# UNO-R3.net
KiCad netlist of a schematic drawn in Altium Designer
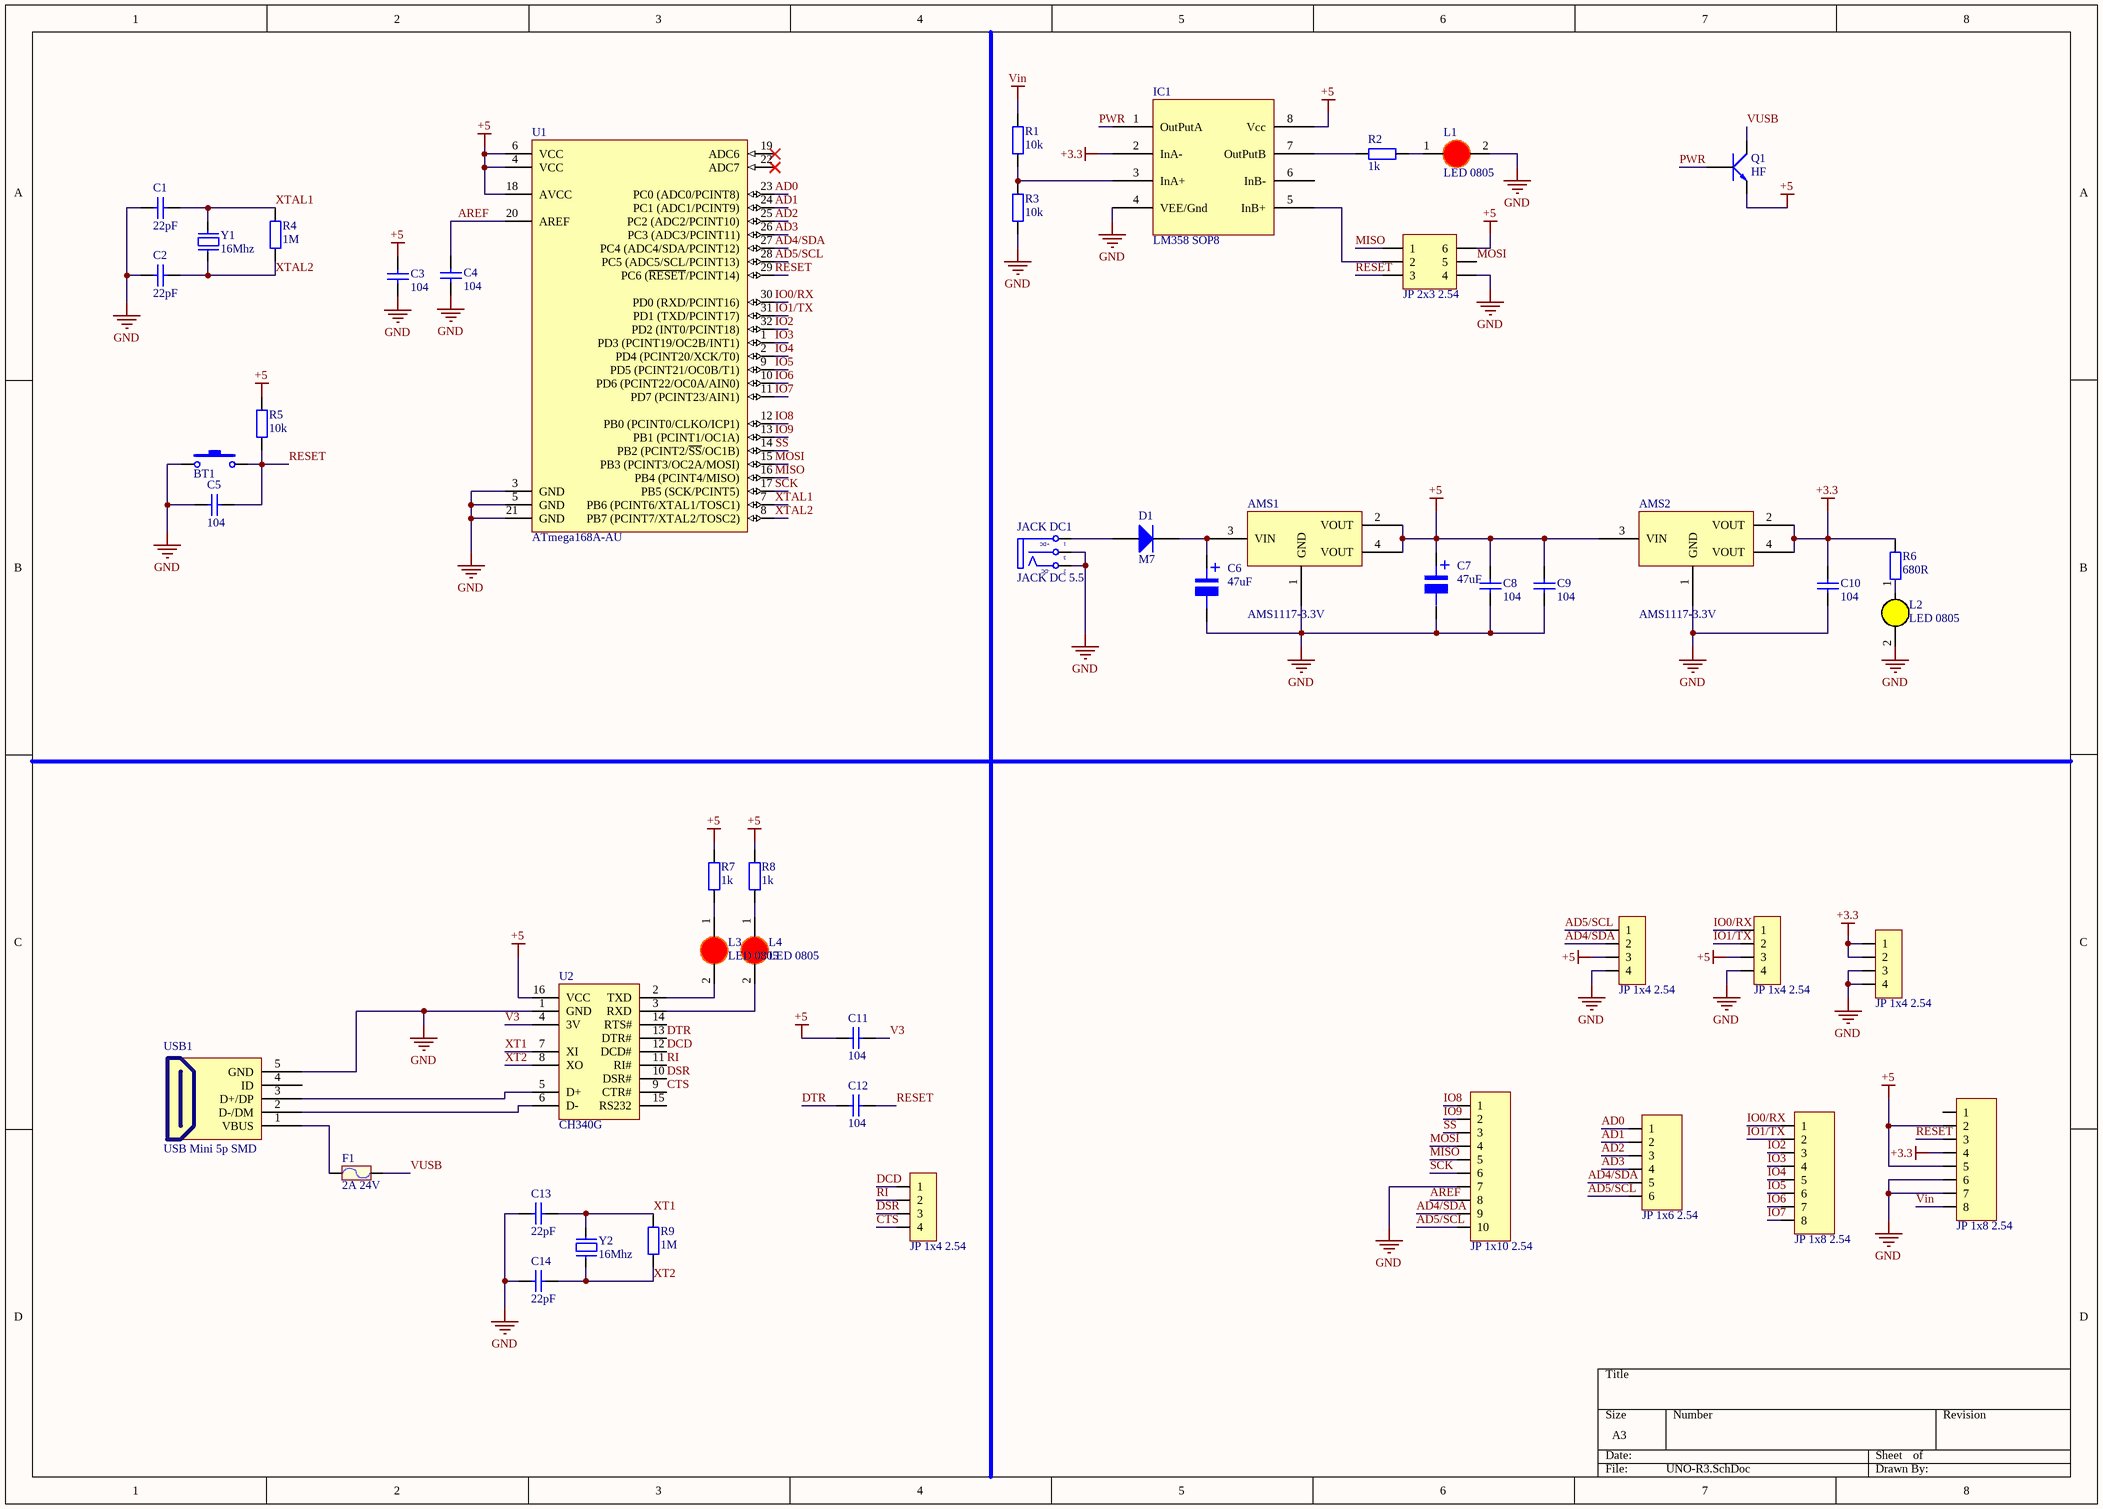
[diagram p0: UNO-R3.SchDoc]

(export (version "E")
  (design (tool "Eeschema 10.0.6"))
  (components
    (comp (ref "AMS1")
      (value "AMS1117-3.3V")
      (footprint "SOT223")
      (description "Dán")
      (libsource (lib "TrungVan_Lib") (part "AMS1117 SMD"))
    )
    (comp (ref "AMS2")
      (value "AMS1117-3.3V")
      (footprint "SOT223")
      (description "Dán")
      (libsource (lib "TrungVan_Lib") (part "AMS1117 SMD"))
    )
    (comp (ref "BT1")
      (value "Nut Nhan 2 Chan SMD 3x6x2.5")
      (footprint "Nut Nhan 2 Chan SMD 3x6x2.5")
      (libsource (lib "TrungVan_Lib") (part "Nut Nhan 2 Chan SMD 3x6x2.5"))
    )
    (comp (ref "C1")
      (value "22pF")
      (footprint "tu 0603")
      (description "Dán")
      (libsource (lib "TrungVan_Lib") (part "Tu 0603 22pF 50V 10%"))
    )
    (comp (ref "C2")
      (value "22pF")
      (footprint "tu 0603")
      (description "Dán")
      (libsource (lib "TrungVan_Lib") (part "Tu 0603 22pF 50V 10%"))
    )
    (comp (ref "C3")
      (value "104")
      (footprint "tu 0603")
      (description "Dán")
      (libsource (lib "TrungVan_Lib") (part "Tu 0603 104 50V 10%"))
    )
    (comp (ref "C4")
      (value "104")
      (footprint "tu 0603")
      (description "Dán")
      (libsource (lib "TrungVan_Lib") (part "Tu 0603 104 50V 10%"))
    )
    (comp (ref "C5")
      (value "104")
      (footprint "tu 0603")
      (description "Dán")
      (libsource (lib "TrungVan_Lib") (part "Tu 0603 104 50V 10%"))
    )
    (comp (ref "C6")
      (value "47uF")
      (footprint "tu nhom 4 (b)")
      (description "Dán")
      (libsource (lib "TrungVan_Lib") (part "Tu Nhom 2.2uF 50V"))
    )
    (comp (ref "C7")
      (value "47uF")
      (footprint "tu nhom 4 (b)")
      (description "Dán")
      (libsource (lib "TrungVan_Lib") (part "Tu Nhom 2.2uF 50V"))
    )
    (comp (ref "C8")
      (value "104")
      (footprint "tu 0402")
      (description "Dán")
      (libsource (lib "TrungVan_Lib") (part "Tu 0402 220nF 6.3V 20%"))
    )
    (comp (ref "C9")
      (value "104")
      (footprint "tu 0402")
      (description "Dán")
      (libsource (lib "TrungVan_Lib") (part "Tu 0402 220nF 6.3V 20%"))
    )
    (comp (ref "C10")
      (value "104")
      (footprint "tu 0402")
      (description "Dán")
      (libsource (lib "TrungVan_Lib") (part "Tu 0402 220nF 6.3V 20%"))
    )
    (comp (ref "C11")
      (value "104")
      (footprint "tu 0603")
      (description "Dán")
      (libsource (lib "TrungVan_Lib") (part "Tu 0603 104 50V 10%"))
    )
    (comp (ref "C12")
      (value "104")
      (footprint "tu 0603")
      (description "Dán")
      (libsource (lib "TrungVan_Lib") (part "Tu 0603 104 50V 10%"))
    )
    (comp (ref "C13")
      (value "22pF")
      (footprint "tu 0603")
      (description "Dán")
      (libsource (lib "TrungVan_Lib") (part "Tu 0603 22pF 50V 10%"))
    )
    (comp (ref "C14")
      (value "22pF")
      (footprint "tu 0603")
      (description "Dán")
      (libsource (lib "TrungVan_Lib") (part "Tu 0603 22pF 50V 10%"))
    )
    (comp (ref "D1")
      (value "M7")
      (footprint "DIODE SMA")
      (description "Dán")
      (libsource (lib "TrungVan_Lib") (part "Diode M7 ( 4007 )"))
    )
    (comp (ref "F1")
      (value "2A 24V")
      (footprint "Cau chi tu phuc hoi 2A 24V SMD1812")
      (description "2A 24V SMD1812")
      (libsource (lib "TrungVan_Lib") (part "Cau chi tu phuc hoi 2A 24V SMD1812"))
    )
    (comp (ref "IC1")
      (value "LM358 SOP8")
      (footprint "SOP 8")
      (description "Dán")
      (libsource (lib "TrungVan_Lib") (part "LM358 SOP8"))
    )
    (comp (ref "JACK DC1")
      (value "JACK DC 5.5")
      (footprint "JACK DC 5.5")
      (libsource (lib "TrungVan_Lib") (part "JACK DC 5.5"))
    )
    (comp (ref "JP1")
      (value "JP 2x3 2.54")
      (footprint "JP 2x3 DT")
      (description "Cắm")
      (libsource (lib "TrungVan_Lib") (part "JP 2x3 2.54 Duc Thang"))
    )
    (comp (ref "JP2")
      (value "JP 1x4 2.54")
      (footprint "JP 1x4 DT")
      (description "Cắm")
      (libsource (lib "TrungVan_Lib") (part "JP 1x4 2.54 Duc Thang"))
    )
    (comp (ref "JP3")
      (value "JP 1x4 2.54")
      (footprint "JP 1x4 DT")
      (description "Cắm")
      (libsource (lib "TrungVan_Lib") (part "JP 1x4 2.54 Duc Thang"))
    )
    (comp (ref "JP4")
      (value "JP 1x4 2.54")
      (footprint "JP 1x4 DT")
      (description "Cắm")
      (libsource (lib "TrungVan_Lib") (part "JP 1x4 2.54 Duc Thang"))
    )
    (comp (ref "JP5")
      (value "JP 1x10 2.54")
      (footprint "JP 1x10 CT")
      (description "Cắm")
      (libsource (lib "TrungVan_Lib") (part "JP 1x10 2.54 Cai Thang"))
    )
    (comp (ref "JP6")
      (value "JP 1x8 2.54")
      (footprint "JP 1x8 CT")
      (description "Cắm")
      (libsource (lib "TrungVan_Lib") (part "JP 1x8 2.54 Cai Thang"))
    )
    (comp (ref "JP7")
      (value "JP 1x8 2.54")
      (footprint "JP 1x8 CT")
      (description "Cắm")
      (libsource (lib "TrungVan_Lib") (part "JP 1x8 2.54 Cai Thang"))
    )
    (comp (ref "JP8")
      (value "JP 1x6 2.54")
      (footprint "JP 1x6 CT")
      (description "Cắm")
      (libsource (lib "TrungVan_Lib") (part "JP 1x6 2.54 Cai Thang"))
    )
    (comp (ref "JP9")
      (value "JP 1x4 2.54")
      (footprint "JP 1x4 DT")
      (description "Cắm")
      (libsource (lib "TrungVan_Lib") (part "JP 1x4 2.54 Duc Thang"))
    )
    (comp (ref "L1")
      (value "LED 0805")
      (footprint "LED-0805-Red")
      (description "Dán")
      (libsource (lib "TrungVan_Lib") (part "LED 0805 Do"))
    )
    (comp (ref "L2")
      (value "LED 0805")
      (footprint "LED-0805-Yellow")
      (description "Dán")
      (libsource (lib "TrungVan_Lib") (part "LED 0805 Vang"))
    )
    (comp (ref "L3")
      (value "LED 0805")
      (footprint "LED-0805-Red")
      (description "Dán")
      (libsource (lib "TrungVan_Lib") (part "LED 0805 Do"))
    )
    (comp (ref "L4")
      (value "LED 0805")
      (footprint "LED-0805-Red")
      (description "Dán")
      (libsource (lib "TrungVan_Lib") (part "LED 0805 Do"))
    )
    (comp (ref "Q1")
      (value "HF")
      (footprint "SOT23")
      (description "NPN transistor")
      (libsource (lib "TrungVan_Lib") (part "C1815 HF SMD"))
    )
    (comp (ref "R1")
      (value "10k")
      (footprint "tro smd 0603")
      (description "Dán")
      (libsource (lib "TrungVan_Lib") (part "Tro 0603 5% 1k"))
    )
    (comp (ref "R2")
      (value "1k")
      (footprint "tro smd 0603")
      (description "Dán")
      (libsource (lib "TrungVan_Lib") (part "Tro 0603 5% 1k"))
    )
    (comp (ref "R3")
      (value "10k")
      (footprint "tro smd 0603")
      (description "Dán")
      (libsource (lib "TrungVan_Lib") (part "Tro 0603 5% 1k"))
    )
    (comp (ref "R4")
      (value "1M")
      (footprint "tro smd 0805")
      (description "Dán")
      (libsource (lib "TrungVan_Lib") (part "Tro 0805 1% 1M"))
    )
    (comp (ref "R5")
      (value "10k")
      (footprint "tro smd 0603")
      (description "Dán")
      (libsource (lib "TrungVan_Lib") (part "Tro 0603 5% 1k"))
    )
    (comp (ref "R6")
      (value "680R")
      (footprint "tro smd 0603")
      (description "Dán")
      (libsource (lib "TrungVan_Lib") (part "Tro 0603 1% 680R"))
    )
    (comp (ref "R7")
      (value "1k")
      (footprint "tro smd 0603")
      (description "Dán")
      (libsource (lib "TrungVan_Lib") (part "Tro 0603 5% 1k"))
    )
    (comp (ref "R8")
      (value "1k")
      (footprint "tro smd 0603")
      (description "Dán")
      (libsource (lib "TrungVan_Lib") (part "Tro 0603 5% 1k"))
    )
    (comp (ref "R9")
      (value "1M")
      (footprint "tro smd 0805")
      (description "Dán")
      (libsource (lib "TrungVan_Lib") (part "Tro 0805 1% 1M"))
    )
    (comp (ref "U1")
      (value "ATmega168A-AU")
      (footprint "TQFP32")
      (fields (field (name "PUBLISHER") "Altium Limited"))
      (libsource (lib "My_Library") (part "ATmega168A-AU"))
    )
    (comp (ref "U2")
      (value "CH340G")
      (footprint "SO16")
      (description "High and Low Side Driver")
      (fields (field (name "PUBLISHER") "Altium Limited"))
      (libsource (lib "My_Library") (part "CH340G"))
    )
    (comp (ref "USB1")
      (value "USB Mini 5p SMD")
      (footprint "USB Mini 5p SMD")
      (description "USB Type B")
      (libsource (lib "TrungVan_Lib") (part "USB Mini 5p SMD"))
    )
    (comp (ref "Y1")
      (value "16Mhz")
      (footprint "Thach Anh 2 chan SMD")
      (description "Crystal For all Crystal 2pin.")
      (libsource (lib "TrungVan_Lib") (part "Thach Anh 2 chan SMD"))
    )
    (comp (ref "Y2")
      (value "16Mhz")
      (footprint "Thach Anh 2 chan SMD")
      (description "Crystal For all Crystal 2pin.")
      (libsource (lib "TrungVan_Lib") (part "Thach Anh 2 chan SMD"))
    )
  )
  (nets
    (net (code "1") (name "+3.3") (class "Default")
      (node (ref "AMS2") (pin "2") (pinfunction "VOUT_2") (pintype "passive"))
      (node (ref "AMS2") (pin "4") (pinfunction "VOUT_4") (pintype "passive"))
      (node (ref "C10") (pin "2") (pinfunction "2_2") (pintype "passive"))
      (node (ref "IC1") (pin "2") (pinfunction "InA-_2") (pintype "passive"))
      (node (ref "JP4") (pin "1") (pinfunction "1_1") (pintype "passive"))
      (node (ref "JP4") (pin "2") (pinfunction "2_2") (pintype "passive"))
      (node (ref "JP6") (pin "4") (pinfunction "4_4") (pintype "passive"))
      (node (ref "R6") (pin "2") (pinfunction "2_2") (pintype "passive"))
    )
    (net (code "2") (name "+5") (class "Default")
      (node (ref "AMS1") (pin "2") (pinfunction "VOUT_2") (pintype "passive"))
      (node (ref "AMS1") (pin "4") (pinfunction "VOUT_4") (pintype "passive"))
      (node (ref "AMS2") (pin "3") (pinfunction "VIN_3") (pintype "passive"))
      (node (ref "C11") (pin "1") (pinfunction "1_1") (pintype "passive"))
      (node (ref "C3") (pin "1") (pinfunction "1_1") (pintype "passive"))
      (node (ref "C7") (pin "1") (pinfunction "1_1") (pintype "passive"))
      (node (ref "C8") (pin "1") (pinfunction "1_1") (pintype "passive"))
      (node (ref "C9") (pin "1") (pinfunction "1_1") (pintype "passive"))
      (node (ref "IC1") (pin "8") (pinfunction "Vcc_8") (pintype "passive"))
      (node (ref "JP1") (pin "6") (pinfunction "6_6") (pintype "passive"))
      (node (ref "JP2") (pin "3") (pinfunction "3_3") (pintype "passive"))
      (node (ref "JP3") (pin "3") (pinfunction "3_3") (pintype "passive"))
      (node (ref "JP6") (pin "2") (pinfunction "2_2") (pintype "passive"))
      (node (ref "JP6") (pin "5") (pinfunction "5_5") (pintype "passive"))
      (node (ref "Q1") (pin "2") (pinfunction "E_2") (pintype "passive"))
      (node (ref "R5") (pin "2") (pinfunction "2_2") (pintype "passive"))
      (node (ref "R7") (pin "2") (pinfunction "2_2") (pintype "passive"))
      (node (ref "R8") (pin "2") (pinfunction "2_2") (pintype "passive"))
      (node (ref "U1") (pin "18") (pinfunction "AVCC_18") (pintype "power_in"))
      (node (ref "U1") (pin "4") (pinfunction "VCC_4") (pintype "power_in"))
      (node (ref "U1") (pin "6") (pinfunction "VCC_6") (pintype "power_in"))
      (node (ref "U2") (pin "16") (pinfunction "VCC_16") (pintype "passive"))
    )
    (net (code "3") (name "/AD0") (class "Default")
      (node (ref "JP8") (pin "1") (pinfunction "1_1") (pintype "passive"))
      (node (ref "U1") (pin "23") (pinfunction "PC0_(ADC0/PCINT8)_23") (pintype "bidirectional"))
    )
    (net (code "4") (name "/AD1") (class "Default")
      (node (ref "JP8") (pin "2") (pinfunction "2_2") (pintype "passive"))
      (node (ref "U1") (pin "24") (pinfunction "PC1_(ADC1/PCINT9)_24") (pintype "bidirectional"))
    )
    (net (code "5") (name "/AD2") (class "Default")
      (node (ref "JP8") (pin "3") (pinfunction "3_3") (pintype "passive"))
      (node (ref "U1") (pin "25") (pinfunction "PC2_(ADC2/PCINT10)_25") (pintype "bidirectional"))
    )
    (net (code "6") (name "/AD3") (class "Default")
      (node (ref "JP8") (pin "4") (pinfunction "4_4") (pintype "passive"))
      (node (ref "U1") (pin "26") (pinfunction "PC3_(ADC3/PCINT11)_26") (pintype "bidirectional"))
    )
    (net (code "7") (name "/AD4{slash}SDA") (class "Default")
      (node (ref "JP2") (pin "2") (pinfunction "2_2") (pintype "passive"))
      (node (ref "JP5") (pin "9") (pinfunction "9_9") (pintype "passive"))
      (node (ref "JP8") (pin "5") (pinfunction "5_5") (pintype "passive"))
      (node (ref "U1") (pin "27") (pinfunction "PC4_(ADC4/SDA/PCINT12)_27") (pintype "bidirectional"))
    )
    (net (code "8") (name "/AD5{slash}SCL") (class "Default")
      (node (ref "JP2") (pin "1") (pinfunction "1_1") (pintype "passive"))
      (node (ref "JP5") (pin "10") (pinfunction "10_10") (pintype "passive"))
      (node (ref "JP8") (pin "6") (pinfunction "6_6") (pintype "passive"))
      (node (ref "U1") (pin "28") (pinfunction "PC5_(ADC5/SCL/PCINT13)_28") (pintype "bidirectional"))
    )
    (net (code "9") (name "/AREF") (class "Default")
      (node (ref "C4") (pin "1") (pinfunction "1_1") (pintype "passive"))
      (node (ref "JP5") (pin "8") (pinfunction "8_8") (pintype "passive"))
      (node (ref "U1") (pin "20") (pinfunction "AREF_20") (pintype "passive"))
    )
    (net (code "10") (name "/CTS") (class "Default")
      (node (ref "JP9") (pin "4") (pinfunction "4_4") (pintype "passive"))
      (node (ref "U2") (pin "9") (pinfunction "CTR#_9") (pintype "passive"))
    )
    (net (code "11") (name "/DCD") (class "Default")
      (node (ref "JP9") (pin "1") (pinfunction "1_1") (pintype "passive"))
      (node (ref "U2") (pin "12") (pinfunction "DCD#_12") (pintype "passive"))
    )
    (net (code "12") (name "/DSR") (class "Default")
      (node (ref "JP9") (pin "3") (pinfunction "3_3") (pintype "passive"))
      (node (ref "U2") (pin "10") (pinfunction "DSR#_10") (pintype "passive"))
    )
    (net (code "13") (name "/DTR") (class "Default")
      (node (ref "C12") (pin "1") (pinfunction "1_1") (pintype "passive"))
      (node (ref "U2") (pin "13") (pinfunction "DTR#_13") (pintype "passive"))
    )
    (net (code "14") (name "/IO0{slash}RX") (class "Default")
      (node (ref "JP3") (pin "1") (pinfunction "1_1") (pintype "passive"))
      (node (ref "JP7") (pin "1") (pinfunction "1_1") (pintype "passive"))
      (node (ref "U1") (pin "30") (pinfunction "PD0_(RXD/PCINT16)_30") (pintype "bidirectional"))
    )
    (net (code "15") (name "/IO1{slash}TX") (class "Default")
      (node (ref "JP3") (pin "2") (pinfunction "2_2") (pintype "passive"))
      (node (ref "JP7") (pin "2") (pinfunction "2_2") (pintype "passive"))
      (node (ref "U1") (pin "31") (pinfunction "PD1_(TXD/PCINT17)_31") (pintype "bidirectional"))
    )
    (net (code "16") (name "/IO2") (class "Default")
      (node (ref "JP7") (pin "3") (pinfunction "3_3") (pintype "passive"))
      (node (ref "U1") (pin "32") (pinfunction "PD2_(INT0/PCINT18)_32") (pintype "bidirectional"))
    )
    (net (code "17") (name "/IO3") (class "Default")
      (node (ref "JP7") (pin "4") (pinfunction "4_4") (pintype "passive"))
      (node (ref "U1") (pin "1") (pinfunction "PD3_(PCINT19/OC2B/INT1)_1") (pintype "bidirectional"))
    )
    (net (code "18") (name "/IO4") (class "Default")
      (node (ref "JP7") (pin "5") (pinfunction "5_5") (pintype "passive"))
      (node (ref "U1") (pin "2") (pinfunction "PD4_(PCINT20/XCK/T0)_2") (pintype "bidirectional"))
    )
    (net (code "19") (name "/IO5") (class "Default")
      (node (ref "JP7") (pin "6") (pinfunction "6_6") (pintype "passive"))
      (node (ref "U1") (pin "9") (pinfunction "PD5_(PCINT21/OC0B/T1)_9") (pintype "bidirectional"))
    )
    (net (code "20") (name "/IO6") (class "Default")
      (node (ref "JP7") (pin "7") (pinfunction "7_7") (pintype "passive"))
      (node (ref "U1") (pin "10") (pinfunction "PD6_(PCINT22/OC0A/AIN0)_10") (pintype "bidirectional"))
    )
    (net (code "21") (name "/IO7") (class "Default")
      (node (ref "JP7") (pin "8") (pinfunction "8_8") (pintype "passive"))
      (node (ref "U1") (pin "11") (pinfunction "PD7_(PCINT23/AIN1)_11") (pintype "bidirectional"))
    )
    (net (code "22") (name "/IO8") (class "Default")
      (node (ref "JP5") (pin "1") (pinfunction "1_1") (pintype "passive"))
      (node (ref "U1") (pin "12") (pinfunction "PB0_(PCINT0/CLKO/ICP1)_12") (pintype "bidirectional"))
    )
    (net (code "23") (name "/IO9") (class "Default")
      (node (ref "JP5") (pin "2") (pinfunction "2_2") (pintype "passive"))
      (node (ref "U1") (pin "13") (pinfunction "PB1_(PCINT1/OC1A)_13") (pintype "bidirectional"))
    )
    (net (code "24") (name "/MISO") (class "Default")
      (node (ref "JP1") (pin "1") (pinfunction "1_1") (pintype "passive"))
      (node (ref "JP5") (pin "5") (pinfunction "5_5") (pintype "passive"))
      (node (ref "U1") (pin "16") (pinfunction "PB4_(PCINT4/MISO)_16") (pintype "bidirectional"))
    )
    (net (code "25") (name "/MOSI") (class "Default")
      (node (ref "JP1") (pin "5") (pinfunction "5_5") (pintype "passive"))
      (node (ref "JP5") (pin "4") (pinfunction "4_4") (pintype "passive"))
      (node (ref "U1") (pin "15") (pinfunction "PB3_(PCINT3/OC2A/MOSI)_15") (pintype "bidirectional"))
    )
    (net (code "26") (name "/PWR") (class "Default")
      (node (ref "IC1") (pin "1") (pinfunction "OutPutA_1") (pintype "passive"))
      (node (ref "Q1") (pin "1") (pinfunction "B_1") (pintype "passive"))
    )
    (net (code "27") (name "/RESET") (class "Default")
      (node (ref "BT1") (pin "2") (pinfunction "2_2") (pintype "passive"))
      (node (ref "C12") (pin "2") (pinfunction "2_2") (pintype "passive"))
      (node (ref "C5") (pin "2") (pinfunction "2_2") (pintype "passive"))
      (node (ref "JP1") (pin "3") (pinfunction "3_3") (pintype "passive"))
      (node (ref "JP6") (pin "3") (pinfunction "3_3") (pintype "passive"))
      (node (ref "R5") (pin "1") (pinfunction "1_1") (pintype "passive"))
      (node (ref "U1") (pin "29") (pinfunction "PC6_(~{RESET}/PCINT14)_29") (pintype "bidirectional"))
    )
    (net (code "28") (name "/RI") (class "Default")
      (node (ref "JP9") (pin "2") (pinfunction "2_2") (pintype "passive"))
      (node (ref "U2") (pin "11") (pinfunction "RI#_11") (pintype "passive"))
    )
    (net (code "29") (name "/SCK") (class "Default")
      (node (ref "JP5") (pin "6") (pinfunction "6_6") (pintype "passive"))
      (node (ref "U1") (pin "17") (pinfunction "PB5_(SCK/PCINT5)_17") (pintype "bidirectional"))
    )
    (net (code "30") (name "/SS") (class "Default")
      (node (ref "JP5") (pin "3") (pinfunction "3_3") (pintype "passive"))
      (node (ref "U1") (pin "14") (pinfunction "PB2_(PCINT2/~{SS}/OC1B)_14") (pintype "bidirectional"))
    )
    (net (code "31") (name "/V3") (class "Default")
      (node (ref "C11") (pin "2") (pinfunction "2_2") (pintype "passive"))
      (node (ref "U2") (pin "4") (pinfunction "3V_4") (pintype "passive"))
    )
    (net (code "32") (name "/VUSB") (class "Default")
      (node (ref "F1") (pin "1") (pinfunction "1_1") (pintype "passive"))
      (node (ref "Q1") (pin "3") (pinfunction "C_3") (pintype "passive"))
    )
    (net (code "33") (name "/XT1") (class "Default")
      (node (ref "C13") (pin "1") (pinfunction "1_1") (pintype "passive"))
      (node (ref "R9") (pin "2") (pinfunction "2_2") (pintype "passive"))
      (node (ref "U2") (pin "7") (pinfunction "XI_7") (pintype "passive"))
      (node (ref "Y2") (pin "2") (pinfunction "2_2") (pintype "passive"))
    )
    (net (code "34") (name "/XT2") (class "Default")
      (node (ref "C14") (pin "1") (pinfunction "1_1") (pintype "passive"))
      (node (ref "R9") (pin "1") (pinfunction "1_1") (pintype "passive"))
      (node (ref "U2") (pin "8") (pinfunction "XO_8") (pintype "passive"))
      (node (ref "Y2") (pin "1") (pinfunction "1_1") (pintype "passive"))
    )
    (net (code "35") (name "/XTAL1") (class "Default")
      (node (ref "C1") (pin "1") (pinfunction "1_1") (pintype "passive"))
      (node (ref "R4") (pin "2") (pinfunction "2_2") (pintype "passive"))
      (node (ref "U1") (pin "7") (pinfunction "PB6_(PCINT6/XTAL1/TOSC1)_7") (pintype "bidirectional"))
      (node (ref "Y1") (pin "2") (pinfunction "2_2") (pintype "passive"))
    )
    (net (code "36") (name "/XTAL2") (class "Default")
      (node (ref "C2") (pin "1") (pinfunction "1_1") (pintype "passive"))
      (node (ref "R4") (pin "1") (pinfunction "1_1") (pintype "passive"))
      (node (ref "U1") (pin "8") (pinfunction "PB7_(PCINT7/XTAL2/TOSC2)_8") (pintype "bidirectional"))
      (node (ref "Y1") (pin "1") (pinfunction "1_1") (pintype "passive"))
    )
    (net (code "37") (name "GND") (class "Default")
      (node (ref "AMS1") (pin "1") (pinfunction "GND_1") (pintype "passive"))
      (node (ref "AMS2") (pin "1") (pinfunction "GND_1") (pintype "passive"))
      (node (ref "BT1") (pin "1") (pinfunction "1_1") (pintype "passive"))
      (node (ref "C1") (pin "2") (pinfunction "2_2") (pintype "passive"))
      (node (ref "C10") (pin "1") (pinfunction "1_1") (pintype "passive"))
      (node (ref "C13") (pin "2") (pinfunction "2_2") (pintype "passive"))
      (node (ref "C14") (pin "2") (pinfunction "2_2") (pintype "passive"))
      (node (ref "C2") (pin "2") (pinfunction "2_2") (pintype "passive"))
      (node (ref "C3") (pin "2") (pinfunction "2_2") (pintype "passive"))
      (node (ref "C4") (pin "2") (pinfunction "2_2") (pintype "passive"))
      (node (ref "C5") (pin "1") (pinfunction "1_1") (pintype "passive"))
      (node (ref "C6") (pin "2") (pinfunction "2_2") (pintype "passive"))
      (node (ref "C7") (pin "2") (pinfunction "2_2") (pintype "passive"))
      (node (ref "C8") (pin "2") (pinfunction "2_2") (pintype "passive"))
      (node (ref "C9") (pin "2") (pinfunction "2_2") (pintype "passive"))
      (node (ref "IC1") (pin "4") (pinfunction "VEE/Gnd_4") (pintype "passive"))
      (node (ref "JACK DC1") (pin "2") (pinfunction "TN_2") (pintype "passive"))
      (node (ref "JACK DC1") (pin "3") (pinfunction "S_3") (pintype "power_in"))
      (node (ref "JP1") (pin "4") (pinfunction "4_4") (pintype "passive"))
      (node (ref "JP2") (pin "4") (pinfunction "4_4") (pintype "passive"))
      (node (ref "JP3") (pin "4") (pinfunction "4_4") (pintype "passive"))
      (node (ref "JP4") (pin "3") (pinfunction "3_3") (pintype "passive"))
      (node (ref "JP4") (pin "4") (pinfunction "4_4") (pintype "passive"))
      (node (ref "JP5") (pin "7") (pinfunction "7_7") (pintype "passive"))
      (node (ref "JP6") (pin "6") (pinfunction "6_6") (pintype "passive"))
      (node (ref "JP6") (pin "7") (pinfunction "7_7") (pintype "passive"))
      (node (ref "L1") (pin "2") (pinfunction "K_2") (pintype "passive"))
      (node (ref "L2") (pin "2") (pinfunction "K_2") (pintype "passive"))
      (node (ref "R3") (pin "1") (pinfunction "1_1") (pintype "passive"))
      (node (ref "U1") (pin "21") (pinfunction "GND_21") (pintype "power_in"))
      (node (ref "U1") (pin "3") (pinfunction "GND_3") (pintype "power_in"))
      (node (ref "U1") (pin "5") (pinfunction "GND_5") (pintype "power_in"))
      (node (ref "U2") (pin "1") (pinfunction "GND_1") (pintype "passive"))
      (node (ref "USB1") (pin "5") (pinfunction "GND_5") (pintype "passive"))
    )
    (net (code "38") (name "Net-(AMS1-VIN)") (class "Default")
      (node (ref "AMS1") (pin "3") (pinfunction "VIN_3") (pintype "passive"))
      (node (ref "C6") (pin "1") (pinfunction "1_1") (pintype "passive"))
      (node (ref "D1") (pin "2") (pinfunction "K_2") (pintype "passive"))
    )
    (net (code "39") (name "Net-(D1-A)") (class "Default")
      (node (ref "D1") (pin "1") (pinfunction "A_1") (pintype "passive"))
      (node (ref "JACK DC1") (pin "1") (pinfunction "T_1") (pintype "passive"))
    )
    (net (code "40") (name "Net-(IC1-InA+)") (class "Default")
      (node (ref "IC1") (pin "3") (pinfunction "InA+_3") (pintype "passive"))
      (node (ref "R1") (pin "1") (pinfunction "1_1") (pintype "passive"))
      (node (ref "R3") (pin "2") (pinfunction "2_2") (pintype "passive"))
    )
    (net (code "41") (name "Net-(IC1-InB+)") (class "Default")
      (node (ref "IC1") (pin "5") (pinfunction "InB+_5") (pintype "passive"))
      (node (ref "JP1") (pin "2") (pinfunction "2_2") (pintype "passive"))
    )
    (net (code "42") (name "Net-(IC1-OutPutB)") (class "Default")
      (node (ref "IC1") (pin "7") (pinfunction "OutPutB_7") (pintype "passive"))
      (node (ref "R2") (pin "2") (pinfunction "2_2") (pintype "passive"))
    )
    (net (code "43") (name "Net-(L1-A)") (class "Default")
      (node (ref "L1") (pin "1") (pinfunction "A_1") (pintype "passive"))
      (node (ref "R2") (pin "1") (pinfunction "1_1") (pintype "passive"))
    )
    (net (code "44") (name "Net-(L2-A)") (class "Default")
      (node (ref "L2") (pin "1") (pinfunction "A_1") (pintype "passive"))
      (node (ref "R6") (pin "1") (pinfunction "1_1") (pintype "passive"))
    )
    (net (code "45") (name "Net-(L3-A)") (class "Default")
      (node (ref "L3") (pin "1") (pinfunction "A_1") (pintype "passive"))
      (node (ref "R7") (pin "1") (pinfunction "1_1") (pintype "passive"))
    )
    (net (code "46") (name "Net-(L3-K)") (class "Default")
      (node (ref "L3") (pin "2") (pinfunction "K_2") (pintype "passive"))
      (node (ref "U2") (pin "2") (pinfunction "TXD_2") (pintype "passive"))
    )
    (net (code "47") (name "Net-(L4-A)") (class "Default")
      (node (ref "L4") (pin "1") (pinfunction "A_1") (pintype "passive"))
      (node (ref "R8") (pin "1") (pinfunction "1_1") (pintype "passive"))
    )
    (net (code "48") (name "Net-(L4-K)") (class "Default")
      (node (ref "L4") (pin "2") (pinfunction "K_2") (pintype "passive"))
      (node (ref "U2") (pin "3") (pinfunction "RXD_3") (pintype "passive"))
    )
    (net (code "49") (name "Net-(U2-D+)") (class "Default")
      (node (ref "U2") (pin "5") (pinfunction "D+_5") (pintype "passive"))
      (node (ref "USB1") (pin "3") (pinfunction "D+/DP_3") (pintype "passive"))
    )
    (net (code "50") (name "Net-(U2-D-)") (class "Default")
      (node (ref "U2") (pin "6") (pinfunction "D-_6") (pintype "passive"))
      (node (ref "USB1") (pin "2") (pinfunction "D-/DM_2") (pintype "passive"))
    )
    (net (code "51") (name "Net-(USB1-VBUS)") (class "Default")
      (node (ref "F1") (pin "2") (pinfunction "2_2") (pintype "passive"))
      (node (ref "USB1") (pin "1") (pinfunction "VBUS_1") (pintype "passive"))
    )
    (net (code "52") (name "Vin") (class "Default")
      (node (ref "JP6") (pin "8") (pinfunction "8_8") (pintype "passive"))
      (node (ref "R1") (pin "2") (pinfunction "2_2") (pintype "passive"))
    )
    (net (code "53") (name "unconnected-(IC1-InB--Pad6)") (class "Default")
      (node (ref "IC1") (pin "6") (pinfunction "InB-_6") (pintype "passive"))
    )
    (net (code "54") (name "unconnected-(JP6-Pad1)") (class "Default")
      (node (ref "JP6") (pin "1") (pinfunction "1_1") (pintype "passive"))
    )
    (net (code "55") (name "unconnected-(U1-ADC6-Pad19)") (class "Default")
      (node (ref "U1") (pin "19") (pinfunction "ADC6_19") (pintype "input+no_connect"))
    )
    (net (code "56") (name "unconnected-(U1-ADC7-Pad22)") (class "Default")
      (node (ref "U1") (pin "22") (pinfunction "ADC7_22") (pintype "input+no_connect"))
    )
    (net (code "57") (name "unconnected-(U2-RS232-Pad15)") (class "Default")
      (node (ref "U2") (pin "15") (pinfunction "RS232_15") (pintype "passive"))
    )
    (net (code "58") (name "unconnected-(U2-RTS#-Pad14)") (class "Default")
      (node (ref "U2") (pin "14") (pinfunction "RTS#_14") (pintype "passive"))
    )
    (net (code "59") (name "unconnected-(USB1-ID-Pad4)") (class "Default")
      (node (ref "USB1") (pin "4") (pinfunction "ID_4") (pintype "passive"))
    )
  )
)
